# 70_Audio_Port.net
KiCad netlist of a schematic drawn in Altium Designer
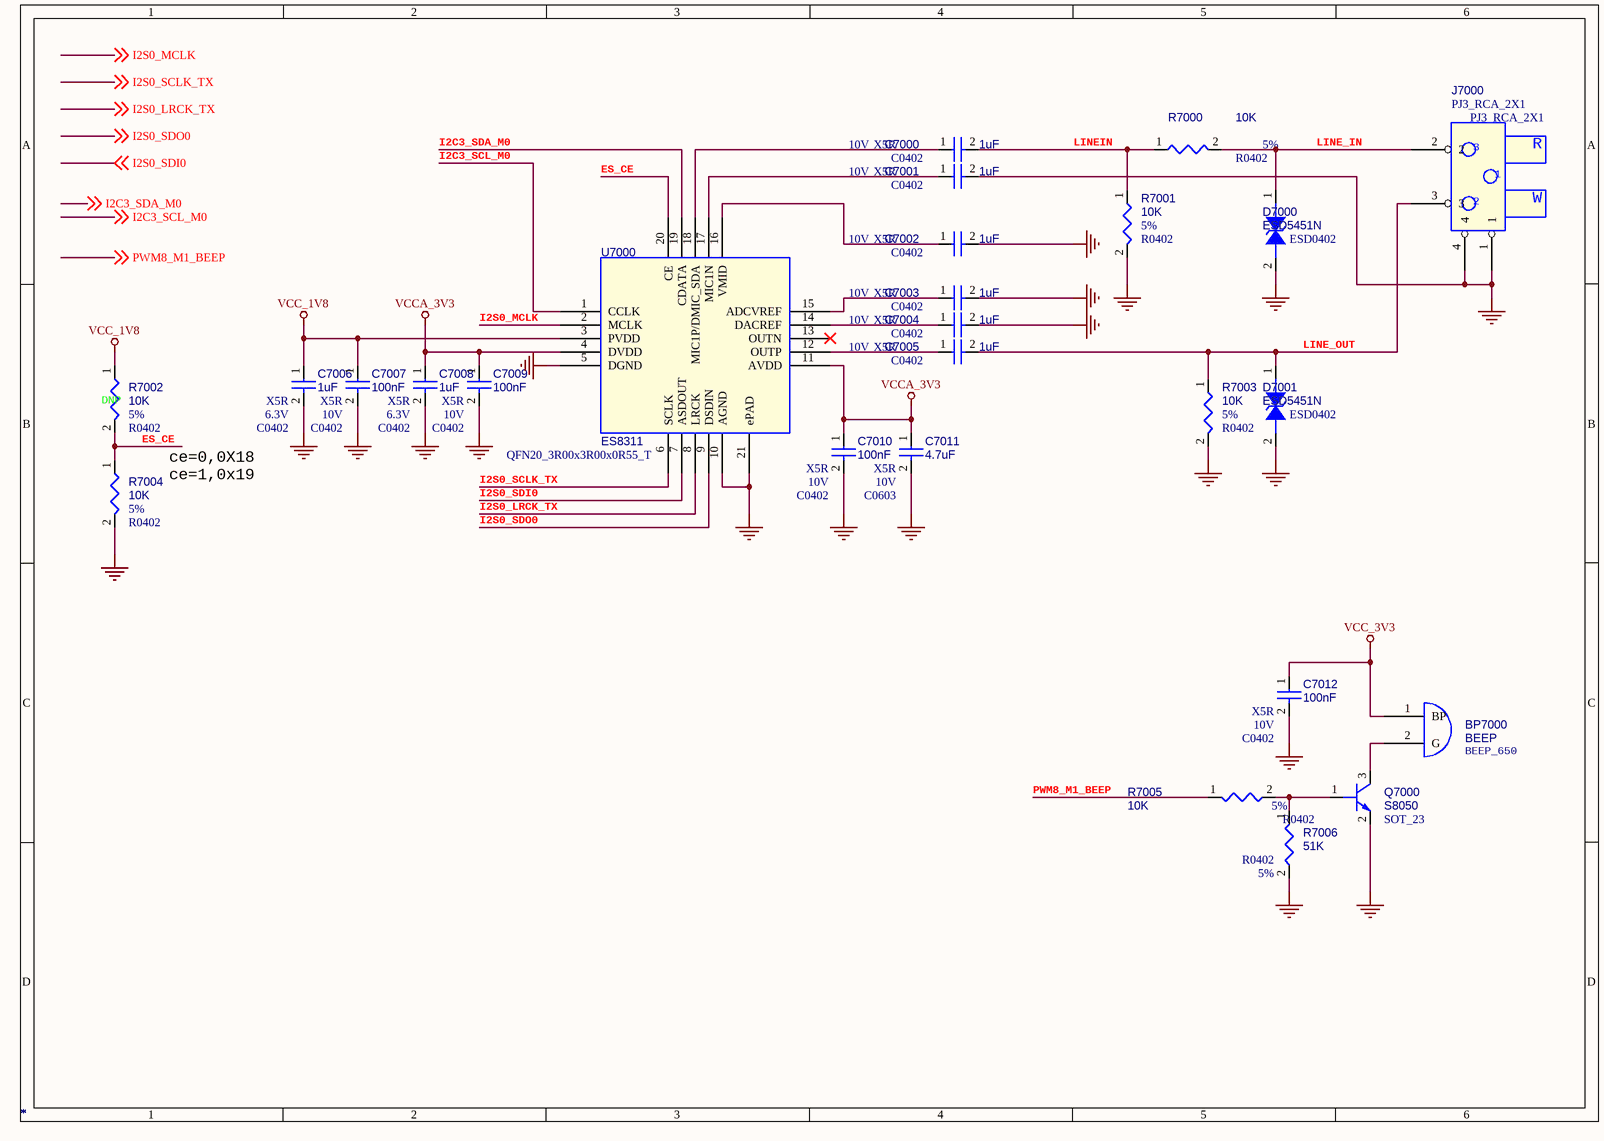
[diagram p0: 70.Audio Port.SchDoc]

(export (version "E")
  (design (tool "Eeschema 10.0.6"))
  (components
    (comp (ref "BP7000")
      (value "*")
      (footprint "BEEP")
      (description "ОЮФґ·дГщЖч,3V,Ц±Іе2P,6.5MMјдѕа,¦µ12X9MM")
      (fields
        (field (name "MANUFACTURER PART NUMBER") "XCMT12A1903PX")
        (field (name "MANUFACTURER") "іЈЦЭОхґєµзЧУУРПЮ№«Лѕ")
        (field (name "PCB FOOTPRINT") "BEEP_650")
        (field (name "ALTIUM_UNNAMED_1") "BEEP")
      )
      (libsource (lib "*") (part "BEEP_0"))
    )
    (comp (ref "C7000")
      (value "*")
      (footprint "C0402")
      (description "cap,1.00uF,+/-10%,10V,X5R,C0402")
      (fields
        (field (name "VOLTAGE") "10V")
        (field (name "PCB FOOTPRINT") "C0402")
        (field (name "DIELECTRIC") "X5R")
        (field (name "MANUFACTURER") "TDK")
        (field (name "TOLERANCE") "10%")
        (field (name "ALTIUM_UNNAMED_1") "1uF")
        (field (name "CREATED BY") "JJJ")
      )
      (libsource (lib "*") (part "CAP NP"))
    )
    (comp (ref "C7001")
      (value "*")
      (footprint "C0402")
      (description "cap,1.00uF,+/-10%,10V,X5R,C0402")
      (fields
        (field (name "VOLTAGE") "10V")
        (field (name "PCB FOOTPRINT") "C0402")
        (field (name "DIELECTRIC") "X5R")
        (field (name "MANUFACTURER") "TDK")
        (field (name "TOLERANCE") "10%")
        (field (name "ALTIUM_UNNAMED_1") "1uF")
        (field (name "CREATED BY") "JJJ")
      )
      (libsource (lib "*") (part "CAP NP"))
    )
    (comp (ref "C7002")
      (value "*")
      (footprint "C0402")
      (description "cap,1.00uF,+/-10%,10V,X5R,C0402")
      (fields
        (field (name "VOLTAGE") "10V")
        (field (name "PCB FOOTPRINT") "C0402")
        (field (name "DIELECTRIC") "X5R")
        (field (name "MANUFACTURER") "TDK")
        (field (name "TOLERANCE") "10%")
        (field (name "ALTIUM_UNNAMED_1") "1uF")
        (field (name "CREATED BY") "JJJ")
      )
      (libsource (lib "*") (part "CAP NP"))
    )
    (comp (ref "C7003")
      (value "*")
      (footprint "C0402")
      (description "cap,1.00uF,+/-10%,10V,X5R,C0402")
      (fields
        (field (name "VOLTAGE") "10V")
        (field (name "PCB FOOTPRINT") "C0402")
        (field (name "DIELECTRIC") "X5R")
        (field (name "MANUFACTURER") "TDK")
        (field (name "TOLERANCE") "10%")
        (field (name "ALTIUM_UNNAMED_1") "1uF")
        (field (name "CREATED BY") "JJJ")
      )
      (libsource (lib "*") (part "CAP NP"))
    )
    (comp (ref "C7004")
      (value "*")
      (footprint "C0402")
      (description "cap,1.00uF,+/-10%,10V,X5R,C0402")
      (fields
        (field (name "VOLTAGE") "10V")
        (field (name "PCB FOOTPRINT") "C0402")
        (field (name "DIELECTRIC") "X5R")
        (field (name "MANUFACTURER") "TDK")
        (field (name "TOLERANCE") "10%")
        (field (name "ALTIUM_UNNAMED_1") "1uF")
        (field (name "CREATED BY") "JJJ")
      )
      (libsource (lib "*") (part "CAP NP"))
    )
    (comp (ref "C7005")
      (value "*")
      (footprint "C0402")
      (description "cap,1.00uF,+/-10%,10V,X5R,C0402")
      (fields
        (field (name "VOLTAGE") "10V")
        (field (name "PCB FOOTPRINT") "C0402")
        (field (name "DIELECTRIC") "X5R")
        (field (name "MANUFACTURER") "TDK")
        (field (name "TOLERANCE") "10%")
        (field (name "ALTIUM_UNNAMED_1") "1uF")
        (field (name "CREATED BY") "JJJ")
      )
      (libsource (lib "*") (part "CAP NP"))
    )
    (comp (ref "C7006")
      (value "*")
      (footprint "C0402")
      (description "cap,1.00uF,+/-10%,6.3V,X5R,C0402")
      (fields
        (field (name "VOLTAGE") "6.3V")
        (field (name "PCB FOOTPRINT") "C0402")
        (field (name "DIELECTRIC") "X5R")
        (field (name "TOLERANCE") "10%")
        (field (name "MANUFACTURER") "TDK")
        (field (name "ALTIUM_UNNAMED_1") "1uF")
        (field (name "CREATED BY") "JJJ")
      )
      (libsource (lib "*") (part "CAP NP"))
    )
    (comp (ref "C7007")
      (value "*")
      (footprint "C0402")
      (description "cap,100.00nF,+/-10%,10V,X5R,C0402")
      (fields
        (field (name "VOLTAGE") "10V")
        (field (name "PCB FOOTPRINT") "C0402")
        (field (name "DIELECTRIC") "X5R")
        (field (name "TOLERANCE") "10%")
        (field (name "MANUFACTURER") "TDK")
        (field (name "ALTIUM_UNNAMED_1") "100nF")
        (field (name "CREATED BY") "JJJ")
      )
      (libsource (lib "*") (part "CAP NP"))
    )
    (comp (ref "C7008")
      (value "*")
      (footprint "C0402")
      (description "cap,1.00uF,+/-10%,6.3V,X5R,C0402")
      (fields
        (field (name "VOLTAGE") "6.3V")
        (field (name "PCB FOOTPRINT") "C0402")
        (field (name "DIELECTRIC") "X5R")
        (field (name "TOLERANCE") "10%")
        (field (name "MANUFACTURER") "TDK")
        (field (name "ALTIUM_UNNAMED_1") "1uF")
        (field (name "CREATED BY") "JJJ")
      )
      (libsource (lib "*") (part "CAP NP"))
    )
    (comp (ref "C7009")
      (value "*")
      (footprint "C0402")
      (description "cap,100.00nF,+/-10%,10V,X5R,C0402")
      (fields
        (field (name "VOLTAGE") "10V")
        (field (name "PCB FOOTPRINT") "C0402")
        (field (name "DIELECTRIC") "X5R")
        (field (name "TOLERANCE") "10%")
        (field (name "MANUFACTURER") "TDK")
        (field (name "ALTIUM_UNNAMED_1") "100nF")
        (field (name "CREATED BY") "JJJ")
      )
      (libsource (lib "*") (part "CAP NP"))
    )
    (comp (ref "C7010")
      (value "*")
      (footprint "C0402")
      (description "cap,100.00nF,+/-10%,10V,X5R,C0402")
      (fields
        (field (name "VOLTAGE") "10V")
        (field (name "PCB FOOTPRINT") "C0402")
        (field (name "DIELECTRIC") "X5R")
        (field (name "MANUFACTURER") "TDK")
        (field (name "TOLERANCE") "10%")
        (field (name "ALTIUM_UNNAMED_1") "100nF")
        (field (name "CREATED BY") "JJJ")
      )
      (libsource (lib "*") (part "CAP NP"))
    )
    (comp (ref "C7011")
      (value "*")
      (footprint "C0603")
      (description "cap,4.70uF,+/-10%,10V,X5R,C0603")
      (fields
        (field (name "VOLTAGE") "10V")
        (field (name "PCB FOOTPRINT") "C0603")
        (field (name "DIELECTRIC") "X5R")
        (field (name "MANUFACTURER") "TDK")
        (field (name "TOLERANCE") "10%")
        (field (name "ALTIUM_UNNAMED_1") "4.7uF")
        (field (name "CREATED BY") "JJJ")
      )
      (libsource (lib "*") (part "CAP NP"))
    )
    (comp (ref "C7012")
      (value "*")
      (footprint "C0402")
      (description "cap,100.00nF,+/-10%,10V,X5R,C0402")
      (fields
        (field (name "VOLTAGE") "10V")
        (field (name "PCB FOOTPRINT") "C0402")
        (field (name "DIELECTRIC") "X5R")
        (field (name "TOLERANCE") "10%")
        (field (name "MANUFACTURER") "TDK")
        (field (name "ALTIUM_UNNAMED_1") "100nF")
        (field (name "CREATED BY") "JJJ")
      )
      (libsource (lib "*") (part "CAP NP"))
    )
    (comp (ref "D7000")
      (value "*")
      (footprint "ESD0402")
      (description "1-Line, Bi-directional, Transient Voltage Suppressors.17.5pF.")
      (fields
        (field (name "PCB FOOTPRINT") "ESD0402")
        (field (name "MANUFACTURER") "WillSemi(О¤¶ы°лµјМе)")
        (field (name "ALTIUM_UNNAMED_1") "ESD5451N")
        (field (name "CREATED BY") "JJJ")
      )
      (libsource (lib "*") (part "DIODE BI_DIR TRIG"))
    )
    (comp (ref "D7001")
      (value "*")
      (footprint "ESD0402")
      (description "1-Line, Bi-directional, Transient Voltage Suppressors.17.5pF.")
      (fields
        (field (name "PCB FOOTPRINT") "ESD0402")
        (field (name "MANUFACTURER") "WillSemi(О¤¶ы°лµјМе)")
        (field (name "ALTIUM_UNNAMED_1") "ESD5451N")
        (field (name "CREATED BY") "JJJ")
      )
      (libsource (lib "*") (part "DIODE BI_DIR TRIG"))
    )
    (comp (ref "J7000")
      (value "*")
      (footprint "AV1-8.4-5G")
      (fields (field (name "PCB FOOTPRINT") "PJ3_RCA_2X1") (field (name "ALTIUM_UNNAMED_1") "PJ3_RCA_2X1"))
      (libsource (lib "*") (part "JP_AV1-8_1.4-5G"))
    )
    (comp (ref "Q7000")
      (value "*")
      (footprint "SOT_23")
      (description "S8050,SOT23")
      (fields
        (field (name "PCB FOOTPRINT") "SOT_23")
        (field (name "MANUFACTURER") "і¤µз")
        (field (name "ALTIUM_UNNAMED_1") "S8050")
        (field (name "CREATED BY") "JJJ")
      )
      (libsource (lib "*") (part "NPN"))
    )
    (comp (ref "R7000")
      (value "*")
      (footprint "R0402")
      (description "НЁУГєсД¤µзЧи,10K,+/-5%,R0402,1/16W.")
      (fields
        (field (name "PCB FOOTPRINT") "R0402")
        (field (name "TOLERANCE") "5%")
        (field (name "MANUFACTURER") "YAGEO")
        (field (name "ALTIUM_UNNAMED_1") "10K")
        (field (name "CREATED BY") "YTL")
      )
      (libsource (lib "*") (part "RESISTOR_Dup1"))
    )
    (comp (ref "R7001")
      (value "*")
      (footprint "R0402")
      (description "НЁУГєсД¤µзЧи,10K,+/-5%,R0402,1/16W.")
      (fields
        (field (name "PCB FOOTPRINT") "R0402")
        (field (name "TOLERANCE") "5%")
        (field (name "MANUFACTURER") "YAGEO")
        (field (name "ALTIUM_UNNAMED_1") "10K")
        (field (name "CREATED BY") "YTL")
      )
      (libsource (lib "*") (part "RESISTOR_Dup1"))
    )
    (comp (ref "R7002")
      (value "*")
      (footprint "R0402")
      (description "НЁУГєсД¤µзЧи,10K,+/-5%,R0402,1/16W.")
      (fields
        (field (name "PCB FOOTPRINT") "R0402")
        (field (name "TOLERANCE") "5%")
        (field (name "OPTION") "DNP")
        (field (name "MANUFACTURER") "YAGEO")
        (field (name "ALTIUM_UNNAMED_1") "10K")
        (field (name "CREATED BY") "YTL")
      )
      (libsource (lib "*") (part "RESISTOR_Dup1"))
    )
    (comp (ref "R7003")
      (value "*")
      (footprint "R0402")
      (description "НЁУГєсД¤µзЧи,10K,+/-5%,R0402,1/16W.")
      (fields
        (field (name "PCB FOOTPRINT") "R0402")
        (field (name "TOLERANCE") "5%")
        (field (name "MANUFACTURER") "YAGEO")
        (field (name "ALTIUM_UNNAMED_1") "10K")
        (field (name "CREATED BY") "YTL")
      )
      (libsource (lib "*") (part "RESISTOR_Dup1"))
    )
    (comp (ref "R7004")
      (value "*")
      (footprint "R0402")
      (description "НЁУГєсД¤µзЧи,10K,+/-5%,R0402,1/16W.")
      (fields
        (field (name "PCB FOOTPRINT") "R0402")
        (field (name "TOLERANCE") "5%")
        (field (name "MANUFACTURER") "YAGEO")
        (field (name "ALTIUM_UNNAMED_1") "10K")
        (field (name "CREATED BY") "YTL")
      )
      (libsource (lib "*") (part "RESISTOR_Dup1"))
    )
    (comp (ref "R7005")
      (value "*")
      (footprint "R0402")
      (description "НЁУГєсД¤µзЧи,10K,+/-5%,R0402,1/16W.")
      (fields
        (field (name "PCB FOOTPRINT") "R0402")
        (field (name "TOLERANCE") "5%")
        (field (name "MANUFACTURER") "YAGEO")
        (field (name "ALTIUM_UNNAMED_1") "10K")
        (field (name "CREATED BY") "YTL")
      )
      (libsource (lib "*") (part "RESISTOR_Dup1"))
    )
    (comp (ref "R7006")
      (value "*")
      (footprint "R0402")
      (description "НЁУГєсД¤µзЧи,51K,+/-5%,R0402,1/16W.")
      (fields
        (field (name "PCB FOOTPRINT") "R0402")
        (field (name "TOLERANCE") "5%")
        (field (name "MANUFACTURER") "YAGEO")
        (field (name "ALTIUM_UNNAMED_1") "51K")
        (field (name "CREATED BY") "YTL")
      )
      (libsource (lib "*") (part "RESISTOR_Dup1"))
    )
    (comp (ref "U7000")
      (value "*")
      (footprint "QFN20_3R00x3R00x0R55_T")
      (description "Low Power Audio CODEC")
      (fields
        (field (name "PCB FOOTPRINT") "QFN20_3R00x3R00x0R55_T")
        (field (name "MANUFACTURER") "EverestЈЁЛіРѕЈ©")
        (field (name "ALTIUM_UNNAMED_1") "ES8311")
        (field (name "CREATED BY") "JJJ")
      )
      (libsource (lib "*") (part "CODEC_ES8316_1"))
    )
  )
  (nets
    (net (code "1") (name "/ES_CE") (class "Default")
      (node (ref "R7002") (pin "2") (pinfunction "2_2") (pintype "passive"))
      (node (ref "R7004") (pin "1") (pinfunction "1_1") (pintype "passive"))
      (node (ref "U7000") (pin "20") (pinfunction "CE_20") (pintype "passive"))
    )
    (net (code "2") (name "/LINEIN") (class "Default")
      (node (ref "C7000") (pin "2") (pinfunction "2_2") (pintype "passive"))
      (node (ref "R7000") (pin "1") (pinfunction "1_1") (pintype "passive"))
      (node (ref "R7001") (pin "1") (pinfunction "1_1") (pintype "passive"))
    )
    (net (code "3") (name "/LINE_IN") (class "Default")
      (node (ref "D7000") (pin "1") (pinfunction "1_1") (pintype "passive"))
      (node (ref "J7000") (pin "2") (pinfunction "2_2") (pintype "passive"))
      (node (ref "R7000") (pin "2") (pinfunction "2_2") (pintype "passive"))
    )
    (net (code "4") (name "/LINE_OUT") (class "Default")
      (node (ref "C7005") (pin "2") (pinfunction "2_2") (pintype "passive"))
      (node (ref "D7001") (pin "1") (pinfunction "1_1") (pintype "passive"))
      (node (ref "J7000") (pin "3") (pinfunction "3_3") (pintype "passive"))
      (node (ref "R7003") (pin "1") (pinfunction "1_1") (pintype "passive"))
    )
    (net (code "5") (name "GND") (class "Default")
      (node (ref "C7001") (pin "2") (pinfunction "2_2") (pintype "passive"))
      (node (ref "C7002") (pin "2") (pinfunction "2_2") (pintype "passive"))
      (node (ref "C7003") (pin "2") (pinfunction "2_2") (pintype "passive"))
      (node (ref "C7004") (pin "2") (pinfunction "2_2") (pintype "passive"))
      (node (ref "C7006") (pin "2") (pinfunction "2_2") (pintype "passive"))
      (node (ref "C7007") (pin "2") (pinfunction "2_2") (pintype "passive"))
      (node (ref "C7008") (pin "2") (pinfunction "2_2") (pintype "passive"))
      (node (ref "C7009") (pin "2") (pinfunction "2_2") (pintype "passive"))
      (node (ref "C7010") (pin "2") (pinfunction "2_2") (pintype "passive"))
      (node (ref "C7011") (pin "2") (pinfunction "2_2") (pintype "passive"))
      (node (ref "C7012") (pin "2") (pinfunction "2_2") (pintype "passive"))
      (node (ref "D7000") (pin "2") (pinfunction "2_2") (pintype "passive"))
      (node (ref "D7001") (pin "2") (pinfunction "2_2") (pintype "passive"))
      (node (ref "J7000") (pin "1") (pinfunction "1_1") (pintype "passive"))
      (node (ref "J7000") (pin "4") (pinfunction "4_4") (pintype "passive"))
      (node (ref "Q7000") (pin "2") (pinfunction "EMITTER_2") (pintype "passive"))
      (node (ref "R7001") (pin "2") (pinfunction "2_2") (pintype "passive"))
      (node (ref "R7003") (pin "2") (pinfunction "2_2") (pintype "passive"))
      (node (ref "R7004") (pin "2") (pinfunction "2_2") (pintype "passive"))
      (node (ref "R7006") (pin "2") (pinfunction "2_2") (pintype "passive"))
      (node (ref "U7000") (pin "10") (pinfunction "AGND_10") (pintype "passive"))
      (node (ref "U7000") (pin "21") (pinfunction "ePAD_21") (pintype "passive"))
      (node (ref "U7000") (pin "5") (pinfunction "DGND_5") (pintype "passive"))
    )
    (net (code "6") (name "I2C3_SCL_M0") (class "Default")
      (node (ref "U7000") (pin "1") (pinfunction "CCLK_1") (pintype "passive"))
    )
    (net (code "7") (name "I2C3_SDA_M0") (class "Default")
      (node (ref "U7000") (pin "19") (pinfunction "CDATA_19") (pintype "passive"))
    )
    (net (code "8") (name "I2S0_LRCK_TX") (class "Default")
      (node (ref "U7000") (pin "8") (pinfunction "LRCK_8") (pintype "passive"))
    )
    (net (code "9") (name "I2S0_MCLK") (class "Default")
      (node (ref "U7000") (pin "2") (pinfunction "MCLK_2") (pintype "passive"))
    )
    (net (code "10") (name "I2S0_SCLK_TX") (class "Default")
      (node (ref "U7000") (pin "6") (pinfunction "SCLK_6") (pintype "passive"))
    )
    (net (code "11") (name "I2S0_SDI0") (class "Default")
      (node (ref "U7000") (pin "7") (pinfunction "ASDOUT_7") (pintype "passive"))
    )
    (net (code "12") (name "I2S0_SDO0") (class "Default")
      (node (ref "U7000") (pin "9") (pinfunction "DSDIN_9") (pintype "passive"))
    )
    (net (code "13") (name "Net-(BP7000-G)") (class "Default")
      (node (ref "BP7000") (pin "2") (pinfunction "G_2") (pintype "passive"))
      (node (ref "Q7000") (pin "3") (pinfunction "COLLECTOR_3") (pintype "passive"))
    )
    (net (code "14") (name "Net-(Q7000-BASE)") (class "Default")
      (node (ref "Q7000") (pin "1") (pinfunction "BASE_1") (pintype "passive"))
      (node (ref "R7005") (pin "2") (pinfunction "2_2") (pintype "passive"))
      (node (ref "R7006") (pin "1") (pinfunction "1_1") (pintype "passive"))
    )
    (net (code "15") (name "Net-(U7000-ADCVREF)") (class "Default")
      (node (ref "C7003") (pin "1") (pinfunction "1_1") (pintype "passive"))
      (node (ref "U7000") (pin "15") (pinfunction "ADCVREF_15") (pintype "passive"))
    )
    (net (code "16") (name "Net-(U7000-DACREF)") (class "Default")
      (node (ref "C7004") (pin "1") (pinfunction "1_1") (pintype "passive"))
      (node (ref "U7000") (pin "14") (pinfunction "DACREF_14") (pintype "passive"))
    )
    (net (code "17") (name "Net-(U7000-MIC1N)") (class "Default")
      (node (ref "C7001") (pin "1") (pinfunction "1_1") (pintype "passive"))
      (node (ref "U7000") (pin "17") (pinfunction "MIC1N_17") (pintype "passive"))
    )
    (net (code "18") (name "Net-(U7000-MIC1P{slash}DMIC_SDA)") (class "Default")
      (node (ref "C7000") (pin "1") (pinfunction "1_1") (pintype "passive"))
      (node (ref "U7000") (pin "18") (pinfunction "MIC1P/DMIC_SDA_18") (pintype "passive"))
    )
    (net (code "19") (name "Net-(U7000-OUTP)") (class "Default")
      (node (ref "C7005") (pin "1") (pinfunction "1_1") (pintype "passive"))
      (node (ref "U7000") (pin "12") (pinfunction "OUTP_12") (pintype "passive"))
    )
    (net (code "20") (name "Net-(U7000-VMID)") (class "Default")
      (node (ref "C7002") (pin "1") (pinfunction "1_1") (pintype "passive"))
      (node (ref "U7000") (pin "16") (pinfunction "VMID_16") (pintype "passive"))
    )
    (net (code "21") (name "PWM8_M1_BEEP") (class "Default")
      (node (ref "R7005") (pin "1") (pinfunction "1_1") (pintype "passive"))
    )
    (net (code "22") (name "VCCA_3V3") (class "Default")
      (node (ref "C7008") (pin "1") (pinfunction "1_1") (pintype "passive"))
      (node (ref "C7009") (pin "1") (pinfunction "1_1") (pintype "passive"))
      (node (ref "C7010") (pin "1") (pinfunction "1_1") (pintype "passive"))
      (node (ref "C7011") (pin "1") (pinfunction "1_1") (pintype "passive"))
      (node (ref "U7000") (pin "11") (pinfunction "AVDD_11") (pintype "passive"))
      (node (ref "U7000") (pin "4") (pinfunction "DVDD_4") (pintype "passive"))
    )
    (net (code "23") (name "VCC_1V8") (class "Default")
      (node (ref "C7006") (pin "1") (pinfunction "1_1") (pintype "passive"))
      (node (ref "C7007") (pin "1") (pinfunction "1_1") (pintype "passive"))
      (node (ref "R7002") (pin "1") (pinfunction "1_1") (pintype "passive"))
      (node (ref "U7000") (pin "3") (pinfunction "PVDD_3") (pintype "passive"))
    )
    (net (code "24") (name "VCC_3V3") (class "Default")
      (node (ref "BP7000") (pin "1") (pinfunction "BP_1") (pintype "passive"))
      (node (ref "C7012") (pin "1") (pinfunction "1_1") (pintype "passive"))
    )
    (net (code "25") (name "unconnected-(U7000-OUTN-Pad13)") (class "Default")
      (node (ref "U7000") (pin "13") (pinfunction "OUTN_13") (pintype "passive+no_connect"))
    )
  )
)
